# proiect_tsc.net
KiCad netlist of a schematic drawn in EAGLE
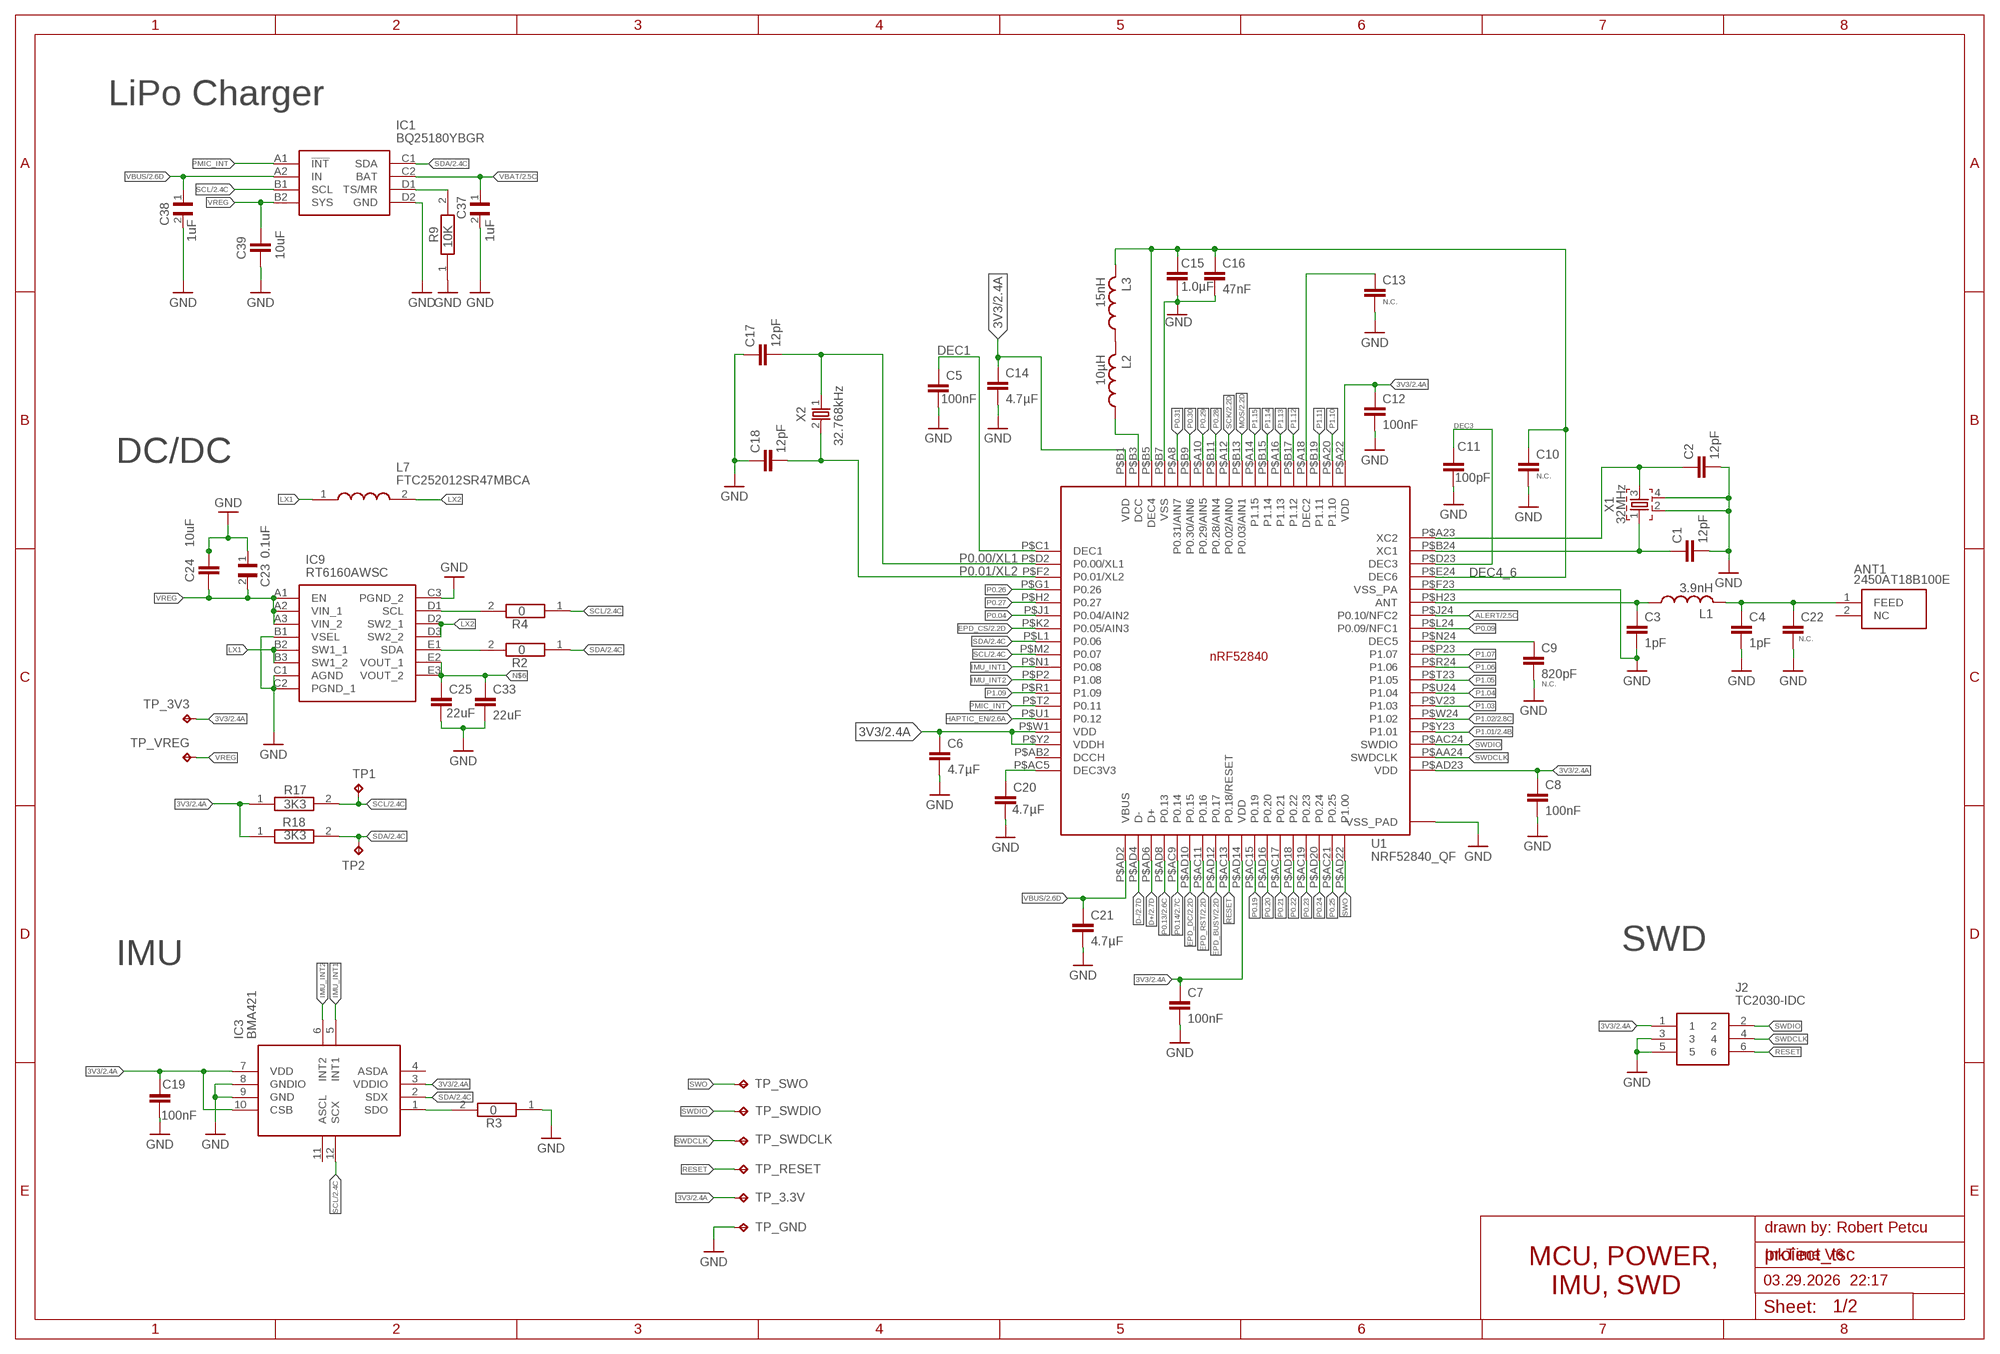
[diagram p0: schematic, sheet 1]
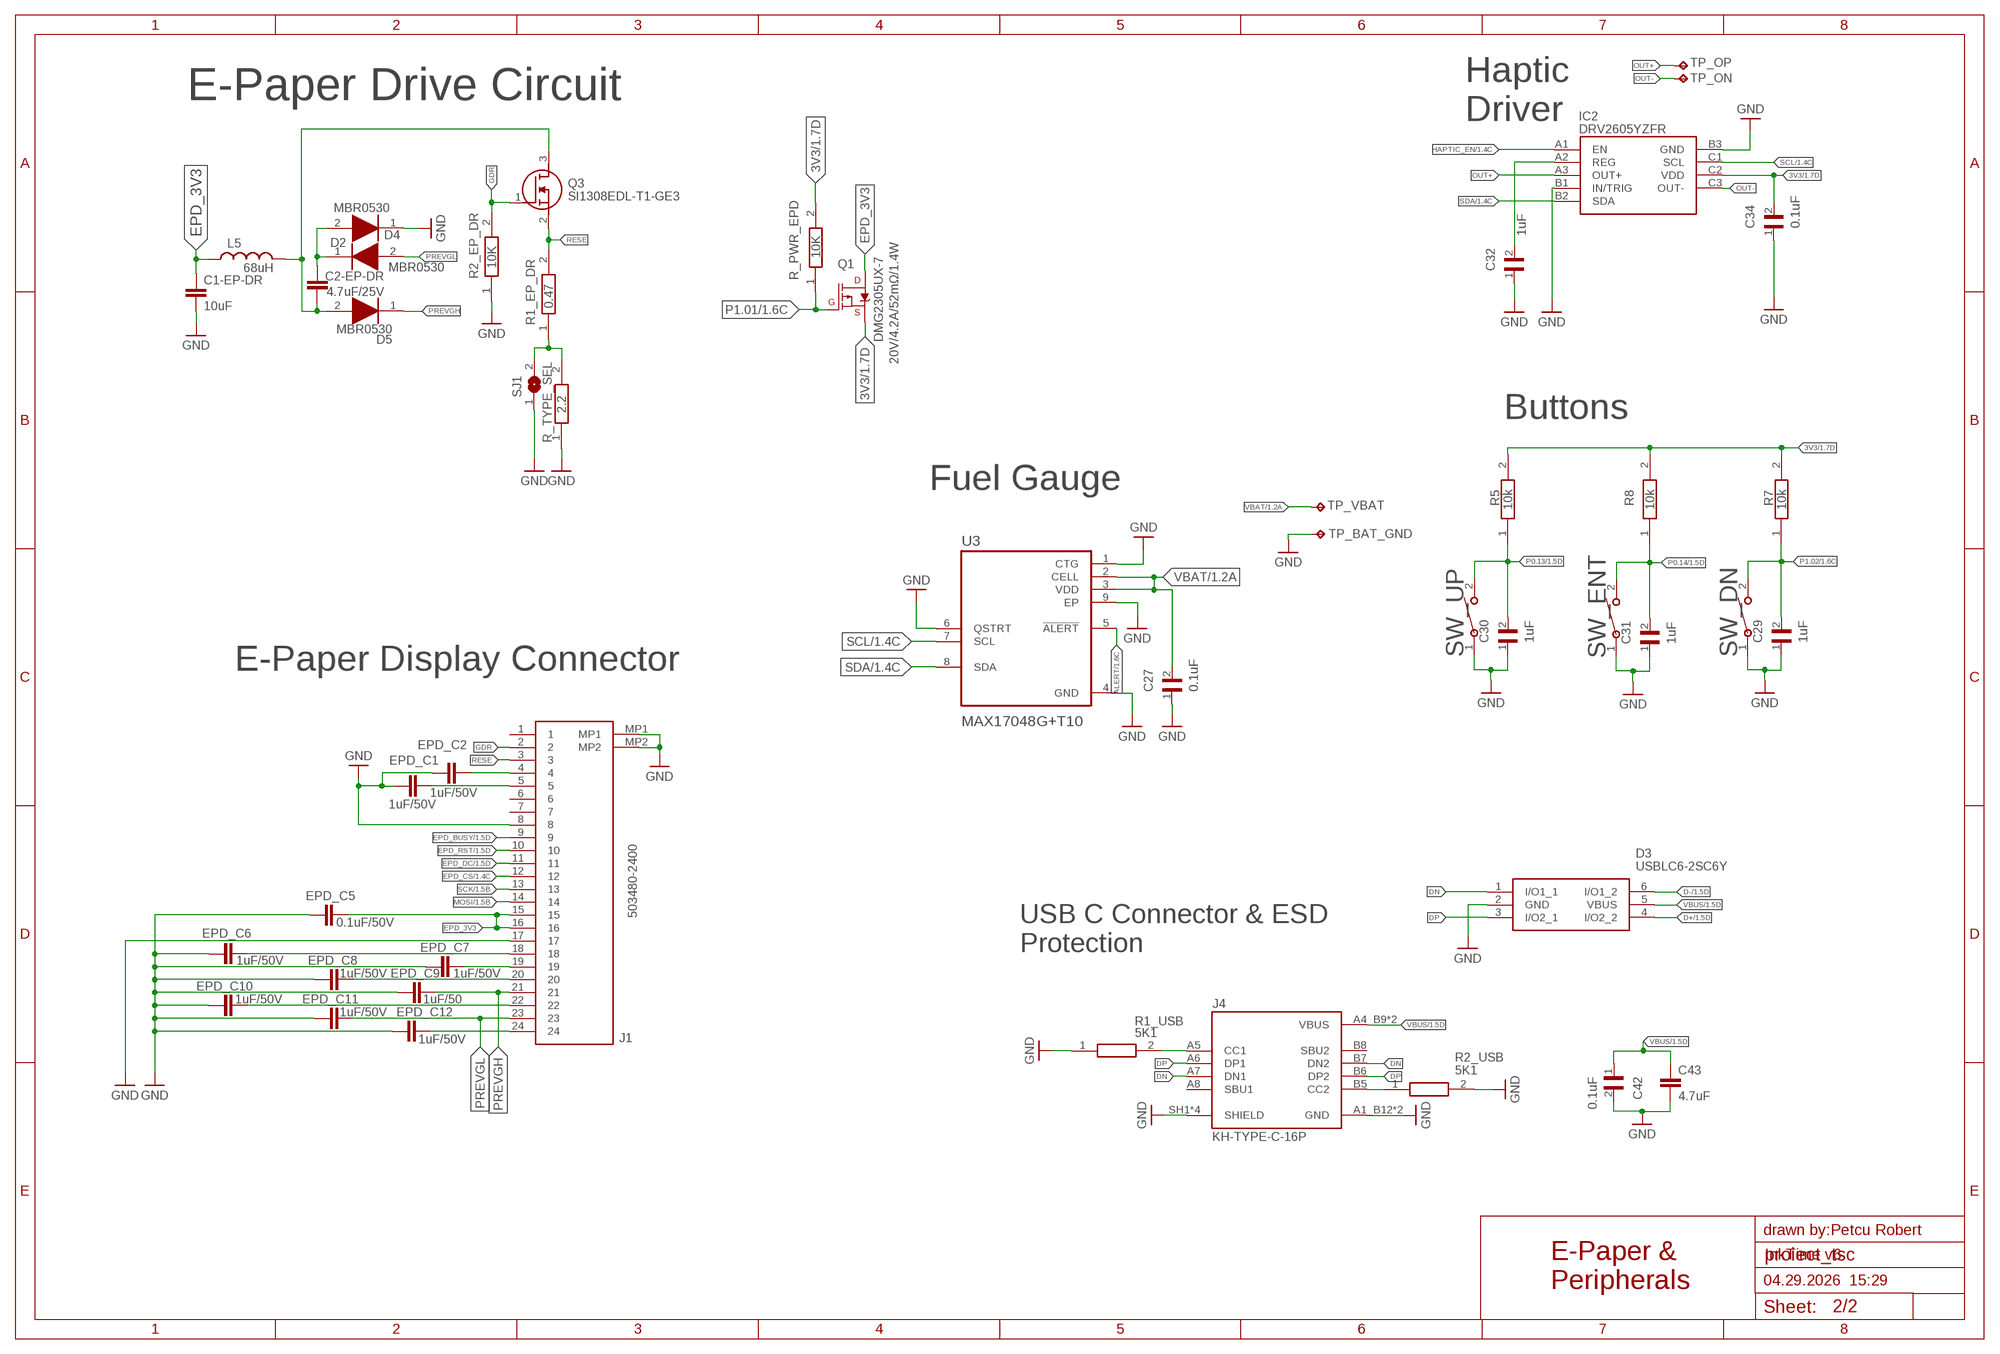
[diagram p1: schematic, sheet 2]

(export (version "E")
  (design (tool "Eeschema 10.0.6"))
  (components
    (comp (ref "C1-EP-DR")
      (value "10uF")
      (footprint "eagle-import:PERFECT_0402_0402")
      (libsource (lib "eagle-import") (part "PERFECT_0402_CAP_0402"))
    )
    (comp (ref "C2-EP-DR")
      (value "4.7uF/25V")
      (footprint "eagle-import:PERFECT_0402_0402")
      (libsource (lib "eagle-import") (part "PERFECT_0402_CAP_0402"))
    )
    (comp (ref "C27")
      (value "0.1uF")
      (footprint "eagle-import:GRM011R60J152KE01L_1_0201")
      (libsource (lib "eagle-import") (part "GRM011R60J152KE01L_1_GRM011R60J152KE01L"))
    )
    (comp (ref "C29")
      (value "1uF")
      (footprint "eagle-import:GRM011R60J152KE01L_1_0201")
      (libsource (lib "eagle-import") (part "GRM011R60J152KE01L_1_GRM011R60J152KE01L"))
    )
    (comp (ref "C30")
      (value "1uF")
      (footprint "eagle-import:GRM011R60J152KE01L_1_0201")
      (libsource (lib "eagle-import") (part "GRM011R60J152KE01L_1_GRM011R60J152KE01L"))
    )
    (comp (ref "C31")
      (value "1uF")
      (footprint "eagle-import:GRM011R60J152KE01L_1_0201")
      (libsource (lib "eagle-import") (part "GRM011R60J152KE01L_1_GRM011R60J152KE01L"))
    )
    (comp (ref "C32")
      (value "1uF")
      (footprint "eagle-import:GRM011R60J152KE01L_1_0201")
      (libsource (lib "eagle-import") (part "GRM011R60J152KE01L_1_GRM011R60J152KE01L"))
    )
    (comp (ref "C34")
      (value "0.1uF")
      (footprint "eagle-import:GRM011R60J152KE01L_1_0201")
      (libsource (lib "eagle-import") (part "GRM011R60J152KE01L_1_GRM011R60J152KE01L"))
    )
    (comp (ref "C42")
      (value "0.1uF")
      (footprint "eagle-import:GRM011R60J152KE01L_1_0201")
      (libsource (lib "eagle-import") (part "GRM011R60J152KE01L_1_GRM011R60J152KE01L"))
    )
    (comp (ref "C43")
      (value "4.7uF")
      (footprint "eagle-import:PERFECT_0402_0402")
      (libsource (lib "eagle-import") (part "PERFECT_0402_CAP_0402"))
    )
    (comp (ref "D2")
      (value "MBR0530")
      (footprint "eagle-import:ESP32_C6_LIBRARY_5_SOD3716X135N")
      (fields (field (name "MF") "ON Semiconductor"))
      (libsource (lib "eagle-import") (part "ESP32_C6_LIBRARY_5_MBR0530"))
    )
    (comp (ref "D3")
      (value "USBLC6-2SC6Y")
      (footprint "eagle-import:ESP32_C6_LIBRARY_3_SOT95P280X145-6N")
      (fields (field (name "MF") "STMicroelectronics"))
      (libsource (lib "eagle-import") (part "ESP32_C6_LIBRARY_3_USBLC6-2SC6Y"))
    )
    (comp (ref "D4")
      (value "MBR0530")
      (footprint "eagle-import:ESP32_C6_LIBRARY_5_SOD3716X135N")
      (fields (field (name "MF") "ON Semiconductor"))
      (libsource (lib "eagle-import") (part "ESP32_C6_LIBRARY_5_MBR0530"))
    )
    (comp (ref "D5")
      (value "MBR0530")
      (footprint "eagle-import:ESP32_C6_LIBRARY_5_SOD3716X135N")
      (fields (field (name "MF") "ON Semiconductor"))
      (libsource (lib "eagle-import") (part "ESP32_C6_LIBRARY_5_MBR0530"))
    )
    (comp (ref "DMG2305UX-7")
      (value "20V/4.2A/52mΩ/1.4W")
      (footprint "eagle-import:ESP32_C6_LIBRARY_4_ESP32_C6_LIBRARY_4_ESP32_C6_LIBRARY_4_ESP32_C6_LIBRARY_4_ESP32_WROVER_SPARKFUN-DISCRETESEMI_SOT23-3")
      (libsource (lib "eagle-import") (part "ESP32_C6_LIBRARY_4_ESP32_WROVER_SPARKFUN-DISCRETESEMI_MOSFET_PCH-DMG2305UX-7"))
    )
    (comp (ref "EPD_C1")
      (value "1uF/50V")
      (footprint "eagle-import:PERFECT_0402_0402")
      (libsource (lib "eagle-import") (part "PERFECT_0402_CAP_0402"))
    )
    (comp (ref "EPD_C2")
      (value "1uF/50V")
      (footprint "eagle-import:PERFECT_0402_0402")
      (libsource (lib "eagle-import") (part "PERFECT_0402_CAP_0402"))
    )
    (comp (ref "EPD_C5")
      (value "0.1uF/50V")
      (footprint "eagle-import:NORDIC_NRF_3_RESC0201_L")
      (libsource (lib "eagle-import") (part "NORDIC_NRF_3_CAPACITOR_0201_L"))
    )
    (comp (ref "EPD_C6")
      (value "1uF/50V")
      (footprint "eagle-import:PERFECT_0402_0402")
      (libsource (lib "eagle-import") (part "PERFECT_0402_CAP_0402"))
    )
    (comp (ref "EPD_C7")
      (value "1uF/50V")
      (footprint "eagle-import:PERFECT_0402_0402")
      (libsource (lib "eagle-import") (part "PERFECT_0402_CAP_0402"))
    )
    (comp (ref "EPD_C8")
      (value "1uF/50V")
      (footprint "eagle-import:PERFECT_0402_0402")
      (libsource (lib "eagle-import") (part "PERFECT_0402_CAP_0402"))
    )
    (comp (ref "EPD_C9")
      (value "1uF/50")
      (footprint "eagle-import:PERFECT_0402_0402")
      (libsource (lib "eagle-import") (part "PERFECT_0402_CAP_0402"))
    )
    (comp (ref "EPD_C10")
      (value "1uF/50V")
      (footprint "eagle-import:PERFECT_0402_0402")
      (libsource (lib "eagle-import") (part "PERFECT_0402_CAP_0402"))
    )
    (comp (ref "EPD_C11")
      (value "1uF/50V")
      (footprint "eagle-import:PERFECT_0402_0402")
      (libsource (lib "eagle-import") (part "PERFECT_0402_CAP_0402"))
    )
    (comp (ref "EPD_C12")
      (value "1uF/50V")
      (footprint "eagle-import:PERFECT_0402_0402")
      (libsource (lib "eagle-import") (part "PERFECT_0402_CAP_0402"))
    )
    (comp (ref "IC2")
      (value "DRV2605YZFR")
      (footprint "eagle-import:DRV2605YZFR_BGA9C50P3X3_144X144X62")
      (libsource (lib "eagle-import") (part "DRV2605YZFR_DRV2605YZFR"))
    )
    (comp (ref "J1")
      (value "503480-2400")
      (footprint "eagle-import:503480-2400_5034802400")
      (fields (field (name "MOUSER_PART_NUMBER") "538-503480-2400"))
      (libsource (lib "eagle-import") (part "503480-2400_503480-2400"))
    )
    (comp (ref "J4")
      (value "KH-TYPE-C-16P")
      (footprint "eagle-import:KH-TYPE-C-16P_KINGHELM_KH-TYPE-C-16P")
      (fields (field (name "MF") "kinghelm"))
      (libsource (lib "eagle-import") (part "KH-TYPE-C-16P_KH-TYPE-C-16P"))
    )
    (comp (ref "L5")
      (value "68uH")
      (footprint "eagle-import:NORDIC_NRF_2_RESC0402_L")
      (libsource (lib "eagle-import") (part "NORDIC_NRF_2_INDUCTOR_0402_L"))
    )
    (comp (ref "Q3")
      (value "SI1308EDL-T1-GE3")
      (footprint "eagle-import:ESP32_C6_LIBRARY_6_SOT65P210X110-3N")
      (fields (field (name "MF") "Vishay Siliconix"))
      (libsource (lib "eagle-import") (part "ESP32_C6_LIBRARY_6_SI1308EDL-T1-GE3"))
    )
    (comp (ref "R1_EP_DR")
      (value "0.47")
      (footprint "eagle-import:CPF0201D7K68C1_0201")
      (libsource (lib "eagle-import") (part "CPF0201D7K68C1_CPF0201D7K68C1"))
    )
    (comp (ref "R1_USB")
      (value "5K1")
      (footprint "eagle-import:CPF0201D7K68C1_0201")
      (libsource (lib "eagle-import") (part "CPF0201D7K68C1_CPF0201D7K68C1"))
    )
    (comp (ref "R2_EP_DR")
      (value "10K")
      (footprint "eagle-import:CPF0201D7K68C1_0201")
      (libsource (lib "eagle-import") (part "CPF0201D7K68C1_CPF0201D7K68C1"))
    )
    (comp (ref "R2_USB")
      (value "5K1")
      (footprint "eagle-import:CPF0201D7K68C1_0201")
      (libsource (lib "eagle-import") (part "CPF0201D7K68C1_CPF0201D7K68C1"))
    )
    (comp (ref "R5")
      (value "10k")
      (footprint "eagle-import:CPF0201D7K68C1_0201")
      (libsource (lib "eagle-import") (part "CPF0201D7K68C1_CPF0201D7K68C1"))
    )
    (comp (ref "R7")
      (value "10k")
      (footprint "eagle-import:CPF0201D7K68C1_0201")
      (libsource (lib "eagle-import") (part "CPF0201D7K68C1_CPF0201D7K68C1"))
    )
    (comp (ref "R8")
      (value "10k")
      (footprint "eagle-import:CPF0201D7K68C1_0201")
      (libsource (lib "eagle-import") (part "CPF0201D7K68C1_CPF0201D7K68C1"))
    )
    (comp (ref "R_PWR_EPD")
      (value "10K")
      (footprint "eagle-import:CPF0201D7K68C1_0201")
      (libsource (lib "eagle-import") (part "CPF0201D7K68C1_CPF0201D7K68C1"))
    )
    (comp (ref "R_TYPE_SEL")
      (value "2.2")
      (footprint "eagle-import:CPF0201D7K68C1_0201")
      (libsource (lib "eagle-import") (part "CPF0201D7K68C1_CPF0201D7K68C1"))
    )
    (comp (ref "SJ1")
      (value "ESP32_C6_LIBRARY_7_JUMPER_SJ")
      (footprint "eagle-import:ESP32_C6_LIBRARY_7_JUMPER_SJ")
      (libsource (lib "eagle-import") (part "ESP32_C6_LIBRARY_7_JUMPER_SJ"))
    )
    (comp (ref "SW_DN")
      (value "2025-10-22_07-23-44_LIBRARY_EVP-AKE31ASW_EVP-AKE31A_PAN")
      (footprint "eagle-import:2025-10-22_07-23-44_LIBRARY_SW_EVP-AKE31A_PAN")
      (fields
        (field (name "MANUFACTURER_PART_NUMBER") "EVP-AKE31A")
        (field (name "COPYRIGHT") "Copyright (C) 2025 Ultra Librarian. All rights reserved.")
      )
      (libsource (lib "eagle-import") (part "2025-10-22_07-23-44_LIBRARY_EVP-AKE31ASW_EVP-AKE31A_PAN"))
    )
    (comp (ref "SW_ENT")
      (value "2025-10-22_07-23-44_LIBRARY_EVP-AKE31ASW_EVP-AKE31A_PAN")
      (footprint "eagle-import:2025-10-22_07-23-44_LIBRARY_SW_EVP-AKE31A_PAN")
      (fields
        (field (name "MANUFACTURER_PART_NUMBER") "EVP-AKE31A")
        (field (name "COPYRIGHT") "Copyright (C) 2025 Ultra Librarian. All rights reserved.")
      )
      (libsource (lib "eagle-import") (part "2025-10-22_07-23-44_LIBRARY_EVP-AKE31ASW_EVP-AKE31A_PAN"))
    )
    (comp (ref "SW_UP")
      (value "2025-10-22_07-23-44_LIBRARY_EVP-AKE31ASW_EVP-AKE31A_PAN")
      (footprint "eagle-import:2025-10-22_07-23-44_LIBRARY_SW_EVP-AKE31A_PAN")
      (fields
        (field (name "MANUFACTURER_PART_NUMBER") "EVP-AKE31A")
        (field (name "COPYRIGHT") "Copyright (C) 2025 Ultra Librarian. All rights reserved.")
      )
      (libsource (lib "eagle-import") (part "2025-10-22_07-23-44_LIBRARY_EVP-AKE31ASW_EVP-AKE31A_PAN"))
    )
    (comp (ref "TP_BAT_GND")
      (value "HECTOR_WATCH_1_TPTP20R")
      (footprint "eagle-import:HECTOR_WATCH_1_TP20R")
      (libsource (lib "eagle-import") (part "HECTOR_WATCH_1_TPTP20R"))
    )
    (comp (ref "TP_ON")
      (value "HECTOR_WATCH_1_TPTP20R")
      (footprint "eagle-import:HECTOR_WATCH_1_TP20R")
      (libsource (lib "eagle-import") (part "HECTOR_WATCH_1_TPTP20R"))
    )
    (comp (ref "TP_OP")
      (value "HECTOR_WATCH_1_TPTP20R")
      (footprint "eagle-import:HECTOR_WATCH_1_TP20R")
      (libsource (lib "eagle-import") (part "HECTOR_WATCH_1_TPTP20R"))
    )
    (comp (ref "TP_VBAT")
      (value "HECTOR_WATCH_1_TPTP20R")
      (footprint "eagle-import:HECTOR_WATCH_1_TP20R")
      (libsource (lib "eagle-import") (part "HECTOR_WATCH_1_TPTP20R"))
    )
    (comp (ref "U3")
      (value "MAX17048G+T10")
      (footprint "eagle-import:ESP32_C6_LIBRARY_SON50P200X200X80-9N")
      (fields (field (name "MF") "Analog Devices"))
      (libsource (lib "eagle-import") (part "ESP32_C6_LIBRARY_MAX17048G+T10"))
    )
    (comp (ref "ANT1")
      (value "2450AT18B100E")
      (footprint "eagle-import:2450AT18B100E_ANTC3216X140N")
      (fields (field (name "MOUSER_PART_NUMBER") "609-2450AT18B100E"))
      (libsource (lib "eagle-import") (part "2450AT18B100E_2450AT18B100E"))
    )
    (comp (ref "C1")
      (value "12pF")
      (footprint "eagle-import:NORDIC_NRF_3_RESC0201_L")
      (libsource (lib "eagle-import") (part "NORDIC_NRF_3_CAPACITOR_0201_L"))
    )
    (comp (ref "C2")
      (value "12pF")
      (footprint "eagle-import:NORDIC_NRF_3_RESC0201_L")
      (libsource (lib "eagle-import") (part "NORDIC_NRF_3_CAPACITOR_0201_L"))
    )
    (comp (ref "C3")
      (value "1pF")
      (footprint "eagle-import:NORDIC_NRF_3_RESC0201_L")
      (libsource (lib "eagle-import") (part "NORDIC_NRF_3_CAPACITOR_0201_L"))
    )
    (comp (ref "C4")
      (value "1pF")
      (footprint "eagle-import:NORDIC_NRF_3_RESC0201_L")
      (libsource (lib "eagle-import") (part "NORDIC_NRF_3_CAPACITOR_0201_L"))
    )
    (comp (ref "C5")
      (value "100nF")
      (footprint "eagle-import:NORDIC_NRF_3_RESC0201_L")
      (libsource (lib "eagle-import") (part "NORDIC_NRF_3_CAPACITOR_0201_L"))
    )
    (comp (ref "C6")
      (value "4.7µF")
      (footprint "eagle-import:PERFECT_0402_0402")
      (libsource (lib "eagle-import") (part "PERFECT_0402_CAP_0402"))
    )
    (comp (ref "C7")
      (value "100nF")
      (footprint "eagle-import:NORDIC_NRF_3_RESC0201_L")
      (libsource (lib "eagle-import") (part "NORDIC_NRF_3_CAPACITOR_0201_L"))
    )
    (comp (ref "C8")
      (value "100nF")
      (footprint "eagle-import:NORDIC_NRF_3_RESC0201_L")
      (libsource (lib "eagle-import") (part "NORDIC_NRF_3_CAPACITOR_0201_L"))
    )
    (comp (ref "C9")
      (value "820pF")
      (footprint "eagle-import:NORDIC_NRF_3_RESC0201_L")
      (libsource (lib "eagle-import") (part "NORDIC_NRF_3_CAPACITOR_0201_L"))
    )
    (comp (ref "C10")
      (value "NORDIC_NRF_3_CAPACITOR_0201_L")
      (footprint "eagle-import:NORDIC_NRF_3_RESC0201_L")
      (libsource (lib "eagle-import") (part "NORDIC_NRF_3_CAPACITOR_0201_L"))
    )
    (comp (ref "C11")
      (value "100pF")
      (footprint "eagle-import:NORDIC_NRF_3_RESC0201_L")
      (libsource (lib "eagle-import") (part "NORDIC_NRF_3_CAPACITOR_0201_L"))
    )
    (comp (ref "C12")
      (value "100nF")
      (footprint "eagle-import:NORDIC_NRF_3_RESC0201_L")
      (libsource (lib "eagle-import") (part "NORDIC_NRF_3_CAPACITOR_0201_L"))
    )
    (comp (ref "C13")
      (value "NORDIC_NRF_3_CAPACITOR_0201_L")
      (footprint "eagle-import:NORDIC_NRF_3_RESC0201_L")
      (libsource (lib "eagle-import") (part "NORDIC_NRF_3_CAPACITOR_0201_L"))
    )
    (comp (ref "C14")
      (value "4.7µF")
      (footprint "eagle-import:PERFECT_0402_0402")
      (libsource (lib "eagle-import") (part "PERFECT_0402_CAP_0402"))
    )
    (comp (ref "C15")
      (value "1.0µF")
      (footprint "eagle-import:PERFECT_0402_0402")
      (libsource (lib "eagle-import") (part "PERFECT_0402_CAP_0402"))
    )
    (comp (ref "C16")
      (value "47nF")
      (footprint "eagle-import:NORDIC_NRF_3_RESC0201_L")
      (libsource (lib "eagle-import") (part "NORDIC_NRF_3_CAPACITOR_0201_L"))
    )
    (comp (ref "C17")
      (value "12pF")
      (footprint "eagle-import:NORDIC_NRF_3_RESC0201_L")
      (libsource (lib "eagle-import") (part "NORDIC_NRF_3_CAPACITOR_0201_L"))
    )
    (comp (ref "C18")
      (value "12pF")
      (footprint "eagle-import:NORDIC_NRF_3_RESC0201_L")
      (libsource (lib "eagle-import") (part "NORDIC_NRF_3_CAPACITOR_0201_L"))
    )
    (comp (ref "C19")
      (value "100nF")
      (footprint "eagle-import:NORDIC_NRF_3_RESC0201_L")
      (libsource (lib "eagle-import") (part "NORDIC_NRF_3_CAPACITOR_0201_L"))
    )
    (comp (ref "C20")
      (value "4.7µF")
      (footprint "eagle-import:PERFECT_0402_0402")
      (libsource (lib "eagle-import") (part "PERFECT_0402_CAP_0402"))
    )
    (comp (ref "C21")
      (value "4.7µF")
      (footprint "eagle-import:PERFECT_0402_0402")
      (libsource (lib "eagle-import") (part "PERFECT_0402_CAP_0402"))
    )
    (comp (ref "C22")
      (value "NORDIC_NRF_3_CAPACITOR_0201_L")
      (footprint "eagle-import:NORDIC_NRF_3_RESC0201_L")
      (libsource (lib "eagle-import") (part "NORDIC_NRF_3_CAPACITOR_0201_L"))
    )
    (comp (ref "C23")
      (value "0.1uF")
      (footprint "eagle-import:GRM011R60J152KE01L_1_0201")
      (libsource (lib "eagle-import") (part "GRM011R60J152KE01L_1_GRM011R60J152KE01L"))
    )
    (comp (ref "C24")
      (value "10uF")
      (footprint "eagle-import:PERFECT_0402_0402")
      (libsource (lib "eagle-import") (part "PERFECT_0402_CAP_0402"))
    )
    (comp (ref "C25")
      (value "22uF")
      (footprint "eagle-import:PERFECT_0402_0402")
      (libsource (lib "eagle-import") (part "PERFECT_0402_CAP_0402"))
    )
    (comp (ref "C33")
      (value "22uF")
      (footprint "eagle-import:PERFECT_0402_0402")
      (libsource (lib "eagle-import") (part "PERFECT_0402_CAP_0402"))
    )
    (comp (ref "C37")
      (value "1uF")
      (footprint "eagle-import:GRM011R60J152KE01L_1_0201")
      (libsource (lib "eagle-import") (part "GRM011R60J152KE01L_1_GRM011R60J152KE01L"))
    )
    (comp (ref "C38")
      (value "1uF")
      (footprint "eagle-import:GRM011R60J152KE01L_1_0201")
      (libsource (lib "eagle-import") (part "GRM011R60J152KE01L_1_GRM011R60J152KE01L"))
    )
    (comp (ref "C39")
      (value "10uF")
      (footprint "eagle-import:PERFECT_0402_0402")
      (libsource (lib "eagle-import") (part "PERFECT_0402_CAP_0402"))
    )
    (comp (ref "IC1")
      (value "BQ25180YBGR")
      (footprint "eagle-import:BQ25180YBGR_BGA8C40P2X4_100X155X50")
      (fields (field (name "MOUSER_PART_NUMBER") "595-BQ25180YBGR"))
      (libsource (lib "eagle-import") (part "BQ25180YBGR_BQ25180YBGR"))
    )
    (comp (ref "IC3")
      (value "BMA421")
      (footprint "eagle-import:BMA423_BMA423")
      (fields (field (name "ARROW_PART_NUMBER") "BMA423") (field (name "MOUSER_PART_NUMBER") "262-BMA423"))
      (libsource (lib "eagle-import") (part "BMA423_BMA423"))
    )
    (comp (ref "IC9")
      (value "RT6160AWSC")
      (footprint "eagle-import:RT6160AWSC_BGA15C40P3X5_140X230X60")
      (fields (field (name "MOUSER_PART_NUMBER") "835-RT6160AWSC"))
      (libsource (lib "eagle-import") (part "RT6160AWSC_RT6160AWSC"))
    )
    (comp (ref "J2")
      (value "TC2030-IDC")
      (footprint "eagle-import:TC2030-IDC_TC2030IDC")
      (libsource (lib "eagle-import") (part "TC2030-IDC_TC2030-IDC"))
    )
    (comp (ref "L1")
      (value "3.9nH")
      (footprint "eagle-import:NORDIC_NRF_2_RESC0402_L")
      (libsource (lib "eagle-import") (part "NORDIC_NRF_2_INDUCTOR_0402_L"))
    )
    (comp (ref "L2")
      (value "10µH")
      (footprint "eagle-import:NORDIC_NRF_2_RESC0402_L")
      (libsource (lib "eagle-import") (part "NORDIC_NRF_2_INDUCTOR_0402_L"))
    )
    (comp (ref "L3")
      (value "15nH")
      (footprint "eagle-import:NORDIC_NRF_2_RESC0402_L")
      (libsource (lib "eagle-import") (part "NORDIC_NRF_2_INDUCTOR_0402_L"))
    )
    (comp (ref "L7")
      (value "FTC252012SR47MBCA")
      (footprint "eagle-import:MLP2016SR47MT0S1_INDC2016X100N")
      (libsource (lib "eagle-import") (part "MLP2016SR47MT0S1_FTC252012SR47MBCA"))
    )
    (comp (ref "R2")
      (value "0")
      (footprint "eagle-import:CPF0201D7K68C1_0201")
      (libsource (lib "eagle-import") (part "CPF0201D7K68C1_CPF0201D7K68C1"))
    )
    (comp (ref "R3")
      (value "0")
      (footprint "eagle-import:CPF0201D7K68C1_0201")
      (libsource (lib "eagle-import") (part "CPF0201D7K68C1_CPF0201D7K68C1"))
    )
    (comp (ref "R4")
      (value "0")
      (footprint "eagle-import:CPF0201D7K68C1_0201")
      (libsource (lib "eagle-import") (part "CPF0201D7K68C1_CPF0201D7K68C1"))
    )
    (comp (ref "R9")
      (value "10K")
      (footprint "eagle-import:CPF0201D7K68C1_0201")
      (libsource (lib "eagle-import") (part "CPF0201D7K68C1_CPF0201D7K68C1"))
    )
    (comp (ref "R17")
      (value "3K3")
      (footprint "eagle-import:CPF0201D7K68C1_0201")
      (libsource (lib "eagle-import") (part "CPF0201D7K68C1_CPF0201D7K68C1"))
    )
    (comp (ref "R18")
      (value "3K3")
      (footprint "eagle-import:CPF0201D7K68C1_0201")
      (libsource (lib "eagle-import") (part "CPF0201D7K68C1_CPF0201D7K68C1"))
    )
    (comp (ref "TP1")
      (value "HECTOR_WATCH_1_TPTP20R")
      (footprint "eagle-import:HECTOR_WATCH_1_TP20R")
      (libsource (lib "eagle-import") (part "HECTOR_WATCH_1_TPTP20R"))
    )
    (comp (ref "TP2")
      (value "HECTOR_WATCH_1_TPTP20R")
      (footprint "eagle-import:HECTOR_WATCH_1_TP20R")
      (libsource (lib "eagle-import") (part "HECTOR_WATCH_1_TPTP20R"))
    )
    (comp (ref "TP_3.3V")
      (value "HECTOR_WATCH_1_TPTP20R")
      (footprint "eagle-import:HECTOR_WATCH_1_TP20R")
      (libsource (lib "eagle-import") (part "HECTOR_WATCH_1_TPTP20R"))
    )
    (comp (ref "TP_3V3")
      (value "HECTOR_WATCH_1_TPTP20R")
      (footprint "eagle-import:HECTOR_WATCH_1_TP20R")
      (libsource (lib "eagle-import") (part "HECTOR_WATCH_1_TPTP20R"))
    )
    (comp (ref "TP_GND")
      (value "HECTOR_WATCH_1_TPTP20R")
      (footprint "eagle-import:HECTOR_WATCH_1_TP20R")
      (libsource (lib "eagle-import") (part "HECTOR_WATCH_1_TPTP20R"))
    )
    (comp (ref "TP_RESET")
      (value "HECTOR_WATCH_1_TPTP20R")
      (footprint "eagle-import:HECTOR_WATCH_1_TP20R")
      (libsource (lib "eagle-import") (part "HECTOR_WATCH_1_TPTP20R"))
    )
    (comp (ref "TP_SWDCLK")
      (value "HECTOR_WATCH_1_TPTP20R")
      (footprint "eagle-import:HECTOR_WATCH_1_TP20R")
      (libsource (lib "eagle-import") (part "HECTOR_WATCH_1_TPTP20R"))
    )
    (comp (ref "TP_SWDIO")
      (value "HECTOR_WATCH_1_TPTP20R")
      (footprint "eagle-import:HECTOR_WATCH_1_TP20R")
      (libsource (lib "eagle-import") (part "HECTOR_WATCH_1_TPTP20R"))
    )
    (comp (ref "TP_SWO")
      (value "HECTOR_WATCH_1_TPTP20R")
      (footprint "eagle-import:HECTOR_WATCH_1_TP20R")
      (libsource (lib "eagle-import") (part "HECTOR_WATCH_1_TPTP20R"))
    )
    (comp (ref "TP_VREG")
      (value "HECTOR_WATCH_1_TPTP20R")
      (footprint "eagle-import:HECTOR_WATCH_1_TP20R")
      (libsource (lib "eagle-import") (part "HECTOR_WATCH_1_TPTP20R"))
    )
    (comp (ref "U1")
      (value "NRF52840_QF")
      (footprint "eagle-import:NORDIC_NRF_4_AQFN50P700X700X85_HS-74N")
      (libsource (lib "eagle-import") (part "NORDIC_NRF_4_NRF52840_QF"))
    )
    (comp (ref "X1")
      (value "32MHz")
      (footprint "eagle-import:NORDIC_NRF_BT-XTAL_2016_N")
      (libsource (lib "eagle-import") (part "NORDIC_NRF_XTAL_32MHZ"))
    )
    (comp (ref "X2")
      (value "32.768kHz")
      (footprint "eagle-import:NORDIC_NRF_1_XTAL_3215_N")
      (libsource (lib "eagle-import") (part "NORDIC_NRF_1_XTAL_32KHZ"))
    )
  )
  (nets
    (net (code "1") (name "3V3{slash}1.7D") (class "Default")
      (node (ref "C34") (pin "2") (pinfunction "2_2") (pintype "passive"))
      (node (ref "DMG2305UX-7") (pin "2") (pinfunction "S_2") (pintype "bidirectional"))
      (node (ref "IC2") (pin "C2") (pinfunction "VDD_C2") (pintype "bidirectional"))
      (node (ref "R5") (pin "2") (pinfunction "2_2") (pintype "bidirectional"))
      (node (ref "R7") (pin "2") (pinfunction "2_2") (pintype "bidirectional"))
      (node (ref "R8") (pin "2") (pinfunction "2_2") (pintype "bidirectional"))
      (node (ref "R_PWR_EPD") (pin "2") (pinfunction "2_2") (pintype "bidirectional"))
    )
    (net (code "2") (name "3V3{slash}2.4A") (class "Default")
      (node (ref "C12") (pin "1") (pinfunction "1_1") (pintype "passive"))
      (node (ref "C14") (pin "1") (pinfunction "1_1") (pintype "passive"))
      (node (ref "C19") (pin "1") (pinfunction "1_1") (pintype "passive"))
      (node (ref "C6") (pin "1") (pinfunction "1_1") (pintype "passive"))
      (node (ref "C7") (pin "1") (pinfunction "1_1") (pintype "passive"))
      (node (ref "C8") (pin "1") (pinfunction "1_1") (pintype "passive"))
      (node (ref "IC3") (pin "10") (pinfunction "CSB_10") (pintype "bidirectional"))
      (node (ref "IC3") (pin "3") (pinfunction "VDDIO_3") (pintype "bidirectional"))
      (node (ref "IC3") (pin "7") (pinfunction "VDD_7") (pintype "bidirectional"))
      (node (ref "J2") (pin "1") (pinfunction "1_1") (pintype "bidirectional"))
      (node (ref "R17") (pin "1") (pinfunction "1_1") (pintype "bidirectional"))
      (node (ref "R18") (pin "1") (pinfunction "1_1") (pintype "bidirectional"))
      (node (ref "TP_3.3V") (pin "TP") (pinfunction "TP_TP") (pintype "input"))
      (node (ref "TP_3V3") (pin "TP") (pinfunction "TP_TP") (pintype "input"))
      (node (ref "U1") (pin "P$A22") (pinfunction "VDD_P$A22") (pintype "power_in"))
      (node (ref "U1") (pin "P$AD14") (pinfunction "VDD_P$AD14") (pintype "power_in"))
      (node (ref "U1") (pin "P$AD23") (pinfunction "VDD_P$AD23") (pintype "power_in"))
      (node (ref "U1") (pin "P$B1") (pinfunction "VDD_P$B1") (pintype "power_in"))
      (node (ref "U1") (pin "P$W1") (pinfunction "VDD_P$W1") (pintype "power_in"))
      (node (ref "U1") (pin "P$Y2") (pinfunction "VDDH_P$Y2") (pintype "power_in"))
    )
    (net (code "3") (name "ALERT{slash}1.6C") (class "Default")
      (node (ref "U3") (pin "5") (pinfunction "~{ALERT}_5") (pintype "output"))
    )
    (net (code "4") (name "ALERT{slash}2.5C") (class "Default")
      (node (ref "U1") (pin "P$J24") (pinfunction "P0.10/NFC2_P$J24") (pintype "bidirectional"))
    )
    (net (code "5") (name "D+{slash}1.5D") (class "Default")
      (node (ref "D3") (pin "4") (pinfunction "I/O2_2_4") (pintype "bidirectional"))
    )
    (net (code "6") (name "D+{slash}2.7D") (class "Default")
      (node (ref "U1") (pin "P$AD6") (pinfunction "D+_P$AD6") (pintype "bidirectional"))
    )
    (net (code "7") (name "D-{slash}1.5D") (class "Default")
      (node (ref "D3") (pin "6") (pinfunction "I/O1_2_6") (pintype "bidirectional"))
    )
    (net (code "8") (name "D-{slash}2.7D") (class "Default")
      (node (ref "U1") (pin "P$AD4") (pinfunction "D-_P$AD4") (pintype "bidirectional"))
    )
    (net (code "9") (name "DEC1") (class "Default")
      (node (ref "C5") (pin "1") (pinfunction "1_1") (pintype "passive"))
      (node (ref "U1") (pin "P$C1") (pinfunction "DEC1_P$C1") (pintype "power_in"))
    )
    (net (code "10") (name "DEC3") (class "Default")
      (node (ref "C11") (pin "1") (pinfunction "1_1") (pintype "passive"))
      (node (ref "U1") (pin "P$D23") (pinfunction "DEC3_P$D23") (pintype "bidirectional"))
    )
    (net (code "11") (name "DEC4_6") (class "Default")
      (node (ref "C10") (pin "1") (pinfunction "1_1") (pintype "passive"))
      (node (ref "C15") (pin "1") (pinfunction "1_1") (pintype "passive"))
      (node (ref "C16") (pin "1") (pinfunction "1_1") (pintype "passive"))
      (node (ref "L3") (pin "2") (pinfunction "2_2") (pintype "passive"))
      (node (ref "U1") (pin "P$B5") (pinfunction "DEC4_P$B5") (pintype "power_in"))
      (node (ref "U1") (pin "P$E24") (pinfunction "DEC6_P$E24") (pintype "bidirectional"))
    )
    (net (code "12") (name "DN") (class "Default")
      (node (ref "D3") (pin "1") (pinfunction "I/O1_1_1") (pintype "bidirectional"))
      (node (ref "J4") (pin "A7") (pinfunction "DN1_A7") (pintype "bidirectional"))
      (node (ref "J4") (pin "B7") (pinfunction "DN2_B7") (pintype "bidirectional"))
    )
    (net (code "13") (name "DP") (class "Default")
      (node (ref "D3") (pin "3") (pinfunction "I/O2_1_3") (pintype "bidirectional"))
      (node (ref "J4") (pin "A6") (pinfunction "DP1_A6") (pintype "bidirectional"))
      (node (ref "J4") (pin "B6") (pinfunction "DP2_B6") (pintype "bidirectional"))
    )
    (net (code "14") (name "EPD_3V3") (class "Default")
      (node (ref "C1-EP-DR") (pin "1") (pinfunction "1_1") (pintype "passive"))
      (node (ref "DMG2305UX-7") (pin "3") (pinfunction "D_3") (pintype "bidirectional"))
      (node (ref "EPD_C5") (pin "2") (pinfunction "2_2") (pintype "passive"))
      (node (ref "J1") (pin "15") (pinfunction "15_15") (pintype "bidirectional"))
      (node (ref "J1") (pin "16") (pinfunction "16_16") (pintype "bidirectional"))
      (node (ref "L5") (pin "1") (pinfunction "1_1") (pintype "passive"))
    )
    (net (code "15") (name "EPD_BUSY{slash}1.5D") (class "Default")
      (node (ref "J1") (pin "9") (pinfunction "9_9") (pintype "bidirectional"))
    )
    (net (code "16") (name "EPD_BUSY{slash}2.2D") (class "Default")
      (node (ref "U1") (pin "P$AD12") (pinfunction "P0.17_P$AD12") (pintype "bidirectional"))
    )
    (net (code "17") (name "EPD_CS{slash}1.4C") (class "Default")
      (node (ref "J1") (pin "12") (pinfunction "12_12") (pintype "bidirectional"))
    )
    (net (code "18") (name "EPD_CS{slash}2.2D") (class "Default")
      (node (ref "U1") (pin "P$K2") (pinfunction "P0.05/AIN3_P$K2") (pintype "bidirectional"))
    )
    (net (code "19") (name "EPD_DC{slash}1.5D") (class "Default")
      (node (ref "J1") (pin "11") (pinfunction "11_11") (pintype "bidirectional"))
    )
    (net (code "20") (name "EPD_DC{slash}2.2D") (class "Default")
      (node (ref "U1") (pin "P$AD10") (pinfunction "P0.15_P$AD10") (pintype "bidirectional"))
    )
    (net (code "21") (name "EPD_RST{slash}1.5D") (class "Default")
      (node (ref "J1") (pin "10") (pinfunction "10_10") (pintype "bidirectional"))
    )
    (net (code "22") (name "EPD_RST{slash}2.2D") (class "Default")
      (node (ref "U1") (pin "P$AC11") (pinfunction "P0.16_P$AC11") (pintype "bidirectional"))
    )
    (net (code "23") (name "GDR") (class "Default")
      (node (ref "J1") (pin "2") (pinfunction "2_2") (pintype "bidirectional"))
      (node (ref "Q3") (pin "1") (pinfunction "G_1") (pintype "bidirectional"))
      (node (ref "R2_EP_DR") (pin "2") (pinfunction "2_2") (pintype "bidirectional"))
    )
    (net (code "24") (name "GND") (class "Default")
      (node (ref "C1") (pin "2") (pinfunction "2_2") (pintype "passive"))
      (node (ref "C1-EP-DR") (pin "2") (pinfunction "2_2") (pintype "passive"))
      (node (ref "C10") (pin "2") (pinfunction "2_2") (pintype "passive"))
      (node (ref "C11") (pin "2") (pinfunction "2_2") (pintype "passive"))
      (node (ref "C12") (pin "2") (pinfunction "2_2") (pintype "passive"))
      (node (ref "C13") (pin "2") (pinfunction "2_2") (pintype "passive"))
      (node (ref "C14") (pin "2") (pinfunction "2_2") (pintype "passive"))
      (node (ref "C15") (pin "2") (pinfunction "2_2") (pintype "passive"))
      (node (ref "C16") (pin "2") (pinfunction "2_2") (pintype "passive"))
      (node (ref "C17") (pin "1") (pinfunction "1_1") (pintype "passive"))
      (node (ref "C18") (pin "1") (pinfunction "1_1") (pintype "passive"))
      (node (ref "C19") (pin "2") (pinfunction "2_2") (pintype "passive"))
      (node (ref "C2") (pin "2") (pinfunction "2_2") (pintype "passive"))
      (node (ref "C20") (pin "2") (pinfunction "2_2") (pintype "passive"))
      (node (ref "C21") (pin "2") (pinfunction "2_2") (pintype "passive"))
      (node (ref "C22") (pin "2") (pinfunction "2_2") (pintype "passive"))
      (node (ref "C23") (pin "1") (pinfunction "1_1") (pintype "passive"))
      (node (ref "C24") (pin "1") (pinfunction "1_1") (pintype "passive"))
      (node (ref "C25") (pin "2") (pinfunction "2_2") (pintype "passive"))
      (node (ref "C27") (pin "1") (pinfunction "1_1") (pintype "passive"))
      (node (ref "C29") (pin "1") (pinfunction "1_1") (pintype "passive"))
      (node (ref "C3") (pin "2") (pinfunction "2_2") (pintype "passive"))
      (node (ref "C30") (pin "1") (pinfunction "1_1") (pintype "passive"))
      (node (ref "C31") (pin "1") (pinfunction "1_1") (pintype "passive"))
      (node (ref "C32") (pin "1") (pinfunction "1_1") (pintype "passive"))
      (node (ref "C33") (pin "2") (pinfunction "2_2") (pintype "passive"))
      (node (ref "C34") (pin "1") (pinfunction "1_1") (pintype "passive"))
      (node (ref "C37") (pin "2") (pinfunction "2_2") (pintype "passive"))
      (node (ref "C38") (pin "2") (pinfunction "2_2") (pintype "passive"))
      (node (ref "C39") (pin "2") (pinfunction "2_2") (pintype "passive"))
      (node (ref "C4") (pin "2") (pinfunction "2_2") (pintype "passive"))
      (node (ref "C42") (pin "2") (pinfunction "2_2") (pintype "passive"))
      (node (ref "C43") (pin "2") (pinfunction "2_2") (pintype "passive"))
      (node (ref "C5") (pin "2") (pinfunction "2_2") (pintype "passive"))
      (node (ref "C6") (pin "2") (pinfunction "2_2") (pintype "passive"))
      (node (ref "C7") (pin "2") (pinfunction "2_2") (pintype "passive"))
      (node (ref "C8") (pin "2") (pinfunction "2_2") (pintype "passive"))
      (node (ref "C9") (pin "2") (pinfunction "2_2") (pintype "passive"))
      (node (ref "D3") (pin "2") (pinfunction "GND_2") (pintype "bidirectional"))
      (node (ref "D4") (pin "1") (pinfunction "K_1") (pintype "bidirectional"))
      (node (ref "EPD_C1") (pin "1") (pinfunction "1_1") (pintype "passive"))
      (node (ref "EPD_C10") (pin "1") (pinfunction "1_1") (pintype "passive"))
      (node (ref "EPD_C11") (pin "1") (pinfunction "1_1") (pintype "passive"))
      (node (ref "EPD_C12") (pin "1") (pinfunction "1_1") (pintype "passive"))
      (node (ref "EPD_C2") (pin "1") (pinfunction "1_1") (pintype "passive"))
      (node (ref "EPD_C5") (pin "1") (pinfunction "1_1") (pintype "passive"))
      (node (ref "EPD_C6") (pin "1") (pinfunction "1_1") (pintype "passive"))
      (node (ref "EPD_C7") (pin "1") (pinfunction "1_1") (pintype "passive"))
      (node (ref "EPD_C8") (pin "1") (pinfunction "1_1") (pintype "passive"))
      (node (ref "EPD_C9") (pin "1") (pinfunction "1_1") (pintype "passive"))
      (node (ref "IC1") (pin "D2") (pinfunction "GND_D2") (pintype "bidirectional"))
      (node (ref "IC2") (pin "B1") (pinfunction "IN/TRIG_B1") (pintype "bidirectional"))
      (node (ref "IC2") (pin "B3") (pinfunction "GND_B3") (pintype "bidirectional"))
      (node (ref "IC3") (pin "8") (pinfunction "GNDIO_8") (pintype "bidirectional"))
      (node (ref "IC3") (pin "9") (pinfunction "GND_9") (pintype "bidirectional"))
      (node (ref "IC9") (pin "B1") (pinfunction "VSEL_B1") (pintype "bidirectional"))
      (node (ref "IC9") (pin "C1") (pinfunction "AGND_C1") (pintype "bidirectional"))
      (node (ref "IC9") (pin "C2") (pinfunction "PGND_1_C2") (pintype "bidirectional"))
      (node (ref "IC9") (pin "C3") (pinfunction "PGND_2_C3") (pintype "bidirectional"))
      (node (ref "J1") (pin "17") (pinfunction "17_17") (pintype "bidirectional"))
      (node (ref "J1") (pin "8") (pinfunction "8_8") (pintype "bidirectional"))
      (node (ref "J1") (pin "MP1") (pinfunction "MP1_MP1") (pintype "bidirectional"))
      (node (ref "J1") (pin "MP2") (pinfunction "MP2_MP2") (pintype "bidirectional"))
      (node (ref "J2") (pin "3") (pinfunction "3_3") (pintype "bidirectional"))
      (node (ref "J2") (pin "5") (pinfunction "5_5") (pintype "bidirectional"))
      (node (ref "J4") (pin "A12_B1") (pinfunction "GND_A12_B1") (pintype "power_in"))
      (node (ref "J4") (pin "A1_B12") (pinfunction "GND_A1_B12") (pintype "power_in"))
      (node (ref "J4") (pin "SH1") (pinfunction "SHIELD_SH1") (pintype "passive"))
      (node (ref "J4") (pin "SH2") (pinfunction "SHIELD_SH2") (pintype "passive"))
      (node (ref "J4") (pin "SH3") (pinfunction "SHIELD_SH3") (pintype "passive"))
      (node (ref "J4") (pin "SH4") (pinfunction "SHIELD_SH4") (pintype "passive"))
      (node (ref "R1_USB") (pin "1") (pinfunction "1_1") (pintype "bidirectional"))
      (node (ref "R2_EP_DR") (pin "1") (pinfunction "1_1") (pintype "bidirectional"))
      (node (ref "R2_USB") (pin "2") (pinfunction "2_2") (pintype "bidirectional"))
      (node (ref "R3") (pin "1") (pinfunction "1_1") (pintype "bidirectional"))
      (node (ref "R9") (pin "1") (pinfunction "1_1") (pintype "bidirectional"))
      (node (ref "R_TYPE_SEL") (pin "1") (pinfunction "1_1") (pintype "bidirectional"))
      (node (ref "SJ1") (pin "1") (pinfunction "1_1") (pintype "passive"))
      (node (ref "SW_DN") (pin "1") (pinfunction "1_1") (pintype "passive"))
      (node (ref "SW_ENT") (pin "1") (pinfunction "1_1") (pintype "passive"))
      (node (ref "SW_UP") (pin "1") (pinfunction "1_1") (pintype "passive"))
      (node (ref "TP_BAT_GND") (pin "TP") (pinfunction "TP_TP") (pintype "input"))
      (node (ref "TP_GND") (pin "TP") (pinfunction "TP_TP") (pintype "input"))
      (node (ref "U1") (pin "P$74") (pinfunction "VSS_PAD_P$74") (pintype "bidirectional"))
      (node (ref "U1") (pin "P$75") (pinfunction "VSS_PAD_P$75") (pintype "bidirectional"))
      (node (ref "U1") (pin "P$76") (pinfunction "VSS_PAD_P$76") (pintype "bidirectional"))
      (node (ref "U1") (pin "P$77") (pinfunction "VSS_PAD_P$77") (pintype "bidirectional"))
      (node (ref "U1") (pin "P$78") (pinfunction "VSS_PAD_P$78") (pintype "bidirectional"))
      (node (ref "U1") (pin "P$79") (pinfunction "VSS_PAD_P$79") (pintype "bidirectional"))
      (node (ref "U1") (pin "P$80") (pinfunction "VSS_PAD_P$80") (pintype "bidirectional"))
      (node (ref "U1") (pin "P$81") (pinfunction "VSS_PAD_P$81") (pintype "bidirectional"))
      (node (ref "U1") (pin "P$82") (pinfunction "VSS_PAD_P$82") (pintype "bidirectional"))
      (node (ref "U1") (pin "P$83") (pinfunction "VSS_PAD_P$83") (pintype "bidirectional"))
      (node (ref "U1") (pin "P$84") (pinfunction "VSS_PAD_P$84") (pintype "bidirectional"))
      (node (ref "U1") (pin "P$85") (pinfunction "VSS_PAD_P$85") (pintype "bidirectional"))
      (node (ref "U1") (pin "P$86") (pinfunction "VSS_PAD_P$86") (pintype "bidirectional"))
      (node (ref "U1") (pin "P$87") (pinfunction "VSS_PAD_P$87") (pintype "bidirectional"))
      (node (ref "U1") (pin "P$88") (pinfunction "VSS_PAD_P$88") (pintype "bidirectional"))
      (node (ref "U1") (pin "P$89") (pinfunction "VSS_PAD_P$89") (pintype "bidirectional"))
      (node (ref "U1") (pin "P$90") (pinfunction "VSS_PAD_P$90") (pintype "bidirectional"))
      (node (ref "U1") (pin "P$B7") (pinfunction "VSS_P$B7") (pintype "power_in"))
      (node (ref "U1") (pin "P$F23") (pinfunction "VSS_PA_P$F23") (pintype "bidirectional"))
      (node (ref "U3") (pin "1") (pinfunction "CTG_1") (pintype "power_in"))
      (node (ref "U3") (pin "4") (pinfunction "GND_4") (pintype "power_in"))
      (node (ref "U3") (pin "6") (pinfunction "QSTRT_6") (pintype "input"))
      (node (ref "U3") (pin "9") (pinfunction "EP_9") (pintype "power_in"))
      (node (ref "X1") (pin "2") (pinfunction "2_2") (pintype "passive"))
      (node (ref "X1") (pin "4") (pinfunction "4_4") (pintype "passive"))
    )
    (net (code "25") (name "HAPTIC_EN{slash}1.4C") (class "Default")
      (node (ref "IC2") (pin "A1") (pinfunction "EN_A1") (pintype "bidirectional"))
    )
    (net (code "26") (name "HAPTIC_EN{slash}2.6A") (class "Default")
      (node (ref "U1") (pin "P$U1") (pinfunction "P0.12_P$U1") (pintype "bidirectional"))
    )
    (net (code "27") (name "IMU_INT1") (class "Default")
      (node (ref "IC3") (pin "5") (pinfunction "INT1_5") (pintype "bidirectional"))
      (node (ref "U1") (pin "P$N1") (pinfunction "P0.08_P$N1") (pintype "bidirectional"))
    )
    (net (code "28") (name "IMU_INT2") (class "Default")
      (node (ref "IC3") (pin "6") (pinfunction "INT2_6") (pintype "bidirectional"))
      (node (ref "U1") (pin "P$P2") (pinfunction "P1.08_P$P2") (pintype "bidirectional"))
    )
    (net (code "29") (name "LX1") (class "Default")
      (node (ref "IC9") (pin "B2") (pinfunction "SW1_1_B2") (pintype "bidirectional"))
      (node (ref "IC9") (pin "B3") (pinfunction "SW1_2_B3") (pintype "bidirectional"))
      (node (ref "L7") (pin "1") (pinfunction "1_1") (pintype "bidirectional"))
    )
    (net (code "30") (name "LX2") (class "Default")
      (node (ref "IC9") (pin "D2") (pinfunction "SW2_1_D2") (pintype "bidirectional"))
      (node (ref "IC9") (pin "D3") (pinfunction "SW2_2_D3") (pintype "bidirectional"))
      (node (ref "L7") (pin "2") (pinfunction "2_2") (pintype "bidirectional"))
    )
    (net (code "31") (name "MOSI{slash}1.5B") (class "Default")
      (node (ref "J1") (pin "14") (pinfunction "14_14") (pintype "bidirectional"))
    )
    (net (code "32") (name "MOS{slash}2.2D") (class "Default")
      (node (ref "U1") (pin "P$B13") (pinfunction "P0.03/AIN1_P$B13") (pintype "bidirectional"))
    )
    (net (code "33") (name "N$6") (class "Default")
      (node (ref "C25") (pin "1") (pinfunction "1_1") (pintype "passive"))
      (node (ref "C33") (pin "1") (pinfunction "1_1") (pintype "passive"))
      (node (ref "IC9") (pin "E2") (pinfunction "VOUT_1_E2") (pintype "bidirectional"))
      (node (ref "IC9") (pin "E3") (pinfunction "VOUT_2_E3") (pintype "bidirectional"))
    )
    (net (code "34") (name "Net-(ANT1-FEED)") (class "Default")
      (node (ref "ANT1") (pin "1") (pinfunction "FEED_1") (pintype "input"))
      (node (ref "C22") (pin "1") (pinfunction "1_1") (pintype "passive"))
      (node (ref "C4") (pin "1") (pinfunction "1_1") (pintype "passive"))
      (node (ref "L1") (pin "2") (pinfunction "2_2") (pintype "passive"))
    )
    (net (code "35") (name "Net-(D2-K)") (class "Default")
      (node (ref "C2-EP-DR") (pin "1") (pinfunction "1_1") (pintype "passive"))
      (node (ref "D2") (pin "1") (pinfunction "K_1") (pintype "bidirectional"))
      (node (ref "D4") (pin "2") (pinfunction "A_2") (pintype "bidirectional"))
    )
    (net (code "36") (name "Net-(D5-A)") (class "Default")
      (node (ref "C2-EP-DR") (pin "2") (pinfunction "2_2") (pintype "passive"))
      (node (ref "D5") (pin "2") (pinfunction "A_2") (pintype "bidirectional"))
      (node (ref "L5") (pin "2") (pinfunction "2_2") (pintype "passive"))
      (node (ref "Q3") (pin "3") (pinfunction "D_3") (pintype "bidirectional"))
    )
    (net (code "37") (name "Net-(EPD_C1-Pad2)") (class "Default")
      (node (ref "EPD_C1") (pin "2") (pinfunction "2_2") (pintype "passive"))
      (node (ref "J1") (pin "5") (pinfunction "5_5") (pintype "bidirectional"))
    )
    (net (code "38") (name "Net-(EPD_C2-Pad2)") (class "Default")
      (node (ref "EPD_C2") (pin "2") (pinfunction "2_2") (pintype "passive"))
      (node (ref "J1") (pin "4") (pinfunction "4_4") (pintype "bidirectional"))
    )
    (net (code "39") (name "Net-(EPD_C6-Pad2)") (class "Default")
      (node (ref "EPD_C6") (pin "2") (pinfunction "2_2") (pintype "passive"))
      (node (ref "J1") (pin "18") (pinfunction "18_18") (pintype "bidirectional"))
    )
    (net (code "40") (name "Net-(EPD_C7-Pad2)") (class "Default")
      (node (ref "EPD_C7") (pin "2") (pinfunction "2_2") (pintype "passive"))
      (node (ref "J1") (pin "19") (pinfunction "19_19") (pintype "bidirectional"))
    )
    (net (code "41") (name "Net-(EPD_C8-Pad2)") (class "Default")
      (node (ref "EPD_C8") (pin "2") (pinfunction "2_2") (pintype "passive"))
      (node (ref "J1") (pin "20") (pinfunction "20_20") (pintype "bidirectional"))
    )
    (net (code "42") (name "Net-(EPD_C10-Pad2)") (class "Default")
      (node (ref "EPD_C10") (pin "2") (pinfunction "2_2") (pintype "passive"))
      (node (ref "J1") (pin "22") (pinfunction "22_22") (pintype "bidirectional"))
    )
    (net (code "43") (name "Net-(EPD_C12-Pad2)") (class "Default")
      (node (ref "EPD_C12") (pin "2") (pinfunction "2_2") (pintype "passive"))
      (node (ref "J1") (pin "24") (pinfunction "24_24") (pintype "bidirectional"))
    )
    (net (code "44") (name "Net-(IC1-TS{slash}MR)") (class "Default")
      (node (ref "IC1") (pin "D1") (pinfunction "TS/MR_D1") (pintype "bidirectional"))
      (node (ref "R9") (pin "2") (pinfunction "2_2") (pintype "bidirectional"))
    )
    (net (code "45") (name "Net-(IC2-REG)") (class "Default")
      (node (ref "C32") (pin "2") (pinfunction "2_2") (pintype "passive"))
      (node (ref "IC2") (pin "A2") (pinfunction "REG_A2") (pintype "bidirectional"))
    )
    (net (code "46") (name "Net-(IC3-SDO)") (class "Default")
      (node (ref "IC3") (pin "1") (pinfunction "SDO_1") (pintype "bidirectional"))
      (node (ref "R3") (pin "2") (pinfunction "2_2") (pintype "bidirectional"))
    )
    (net (code "47") (name "Net-(IC9-SCL)") (class "Default")
      (node (ref "IC9") (pin "D1") (pinfunction "SCL_D1") (pintype "bidirectional"))
      (node (ref "R4") (pin "2") (pinfunction "2_2") (pintype "bidirectional"))
    )
    (net (code "48") (name "Net-(IC9-SDA)") (class "Default")
      (node (ref "IC9") (pin "E1") (pinfunction "SDA_E1") (pintype "bidirectional"))
      (node (ref "R2") (pin "2") (pinfunction "2_2") (pintype "bidirectional"))
    )
    (net (code "49") (name "Net-(J4-CC1)") (class "Default")
      (node (ref "J4") (pin "A5") (pinfunction "CC1_A5") (pintype "bidirectional"))
      (node (ref "R1_USB") (pin "2") (pinfunction "2_2") (pintype "bidirectional"))
    )
    (net (code "50") (name "Net-(J4-CC2)") (class "Default")
      (node (ref "J4") (pin "B5") (pinfunction "CC2_B5") (pintype "bidirectional"))
      (node (ref "R2_USB") (pin "1") (pinfunction "1_1") (pintype "bidirectional"))
    )
    (net (code "51") (name "Net-(L2-Pad2)") (class "Default")
      (node (ref "L2") (pin "2") (pinfunction "2_2") (pintype "passive"))
      (node (ref "L3") (pin "1") (pinfunction "1_1") (pintype "passive"))
    )
    (net (code "52") (name "Net-(R1_EP_DR-Pad1)") (class "Default")
      (node (ref "R1_EP_DR") (pin "1") (pinfunction "1_1") (pintype "bidirectional"))
      (node (ref "R_TYPE_SEL") (pin "2") (pinfunction "2_2") (pintype "bidirectional"))
      (node (ref "SJ1") (pin "2") (pinfunction "2_2") (pintype "passive"))
    )
    (net (code "53") (name "Net-(U1-ANT)") (class "Default")
      (node (ref "C3") (pin "1") (pinfunction "1_1") (pintype "passive"))
      (node (ref "L1") (pin "1") (pinfunction "1_1") (pintype "passive"))
      (node (ref "U1") (pin "P$H23") (pinfunction "ANT_P$H23") (pintype "bidirectional"))
    )
    (net (code "54") (name "Net-(U1-DCC)") (class "Default")
      (node (ref "L2") (pin "1") (pinfunction "1_1") (pintype "passive"))
      (node (ref "U1") (pin "P$B3") (pinfunction "DCC_P$B3") (pintype "output"))
    )
    (net (code "55") (name "Net-(U1-DEC2)") (class "Default")
      (node (ref "C13") (pin "1") (pinfunction "1_1") (pintype "passive"))
      (node (ref "U1") (pin "P$A18") (pinfunction "DEC2_P$A18") (pintype "bidirectional"))
    )
    (net (code "56") (name "Net-(U1-DEC3V3)") (class "Default")
      (node (ref "C20") (pin "1") (pinfunction "1_1") (pintype "passive"))
      (node (ref "U1") (pin "P$AC5") (pinfunction "DEC3V3_P$AC5") (pintype "bidirectional"))
    )
    (net (code "57") (name "Net-(U1-DEC5)") (class "Default")
      (node (ref "C9") (pin "1") (pinfunction "1_1") (pintype "passive"))
      (node (ref "U1") (pin "P$N24") (pinfunction "DEC5_P$N24") (pintype "bidirectional"))
    )
    (net (code "58") (name "Net-(U1-XC1)") (class "Default")
      (node (ref "C1") (pin "1") (pinfunction "1_1") (pintype "passive"))
      (node (ref "U1") (pin "P$B24") (pinfunction "XC1_P$B24") (pintype "input"))
      (node (ref "X1") (pin "1") (pinfunction "1_1") (pintype "passive"))
    )
    (net (code "59") (name "Net-(U1-XC2)") (class "Default")
      (node (ref "C2") (pin "1") (pinfunction "1_1") (pintype "passive"))
      (node (ref "U1") (pin "P$A23") (pinfunction "XC2_P$A23") (pintype "output"))
      (node (ref "X1") (pin "3") (pinfunction "3_3") (pintype "passive"))
    )
    (net (code "60") (name "OUT+") (class "Default")
      (node (ref "IC2") (pin "A3") (pinfunction "OUT+_A3") (pintype "bidirectional"))
      (node (ref "TP_OP") (pin "TP") (pinfunction "TP_TP") (pintype "input"))
    )
    (net (code "61") (name "OUT-") (class "Default")
      (node (ref "IC2") (pin "C3") (pinfunction "OUT-_C3") (pintype "bidirectional"))
      (node (ref "TP_ON") (pin "TP") (pinfunction "TP_TP") (pintype "input"))
    )
    (net (code "62") (name "P0.00{slash}XL1") (class "Default")
      (node (ref "C17") (pin "2") (pinfunction "2_2") (pintype "passive"))
      (node (ref "U1") (pin "P$D2") (pinfunction "P0.00/XL1_P$D2") (pintype "bidirectional"))
      (node (ref "X2") (pin "1") (pinfunction "1_1") (pintype "passive"))
    )
    (net (code "63") (name "P0.01{slash}XL2") (class "Default")
      (node (ref "C18") (pin "2") (pinfunction "2_2") (pintype "passive"))
      (node (ref "U1") (pin "P$F2") (pinfunction "P0.01/XL2_P$F2") (pintype "bidirectional"))
      (node (ref "X2") (pin "2") (pinfunction "2_2") (pintype "passive"))
    )
    (net (code "64") (name "P0.04") (class "Default")
      (node (ref "U1") (pin "P$J1") (pinfunction "P0.04/AIN2_P$J1") (pintype "bidirectional"))
    )
    (net (code "65") (name "P0.09") (class "Default")
      (node (ref "U1") (pin "P$L24") (pinfunction "P0.09/NFC1_P$L24") (pintype "bidirectional"))
    )
    (net (code "66") (name "P0.13{slash}1.5D") (class "Default")
      (node (ref "C30") (pin "2") (pinfunction "2_2") (pintype "passive"))
      (node (ref "R5") (pin "1") (pinfunction "1_1") (pintype "bidirectional"))
      (node (ref "SW_UP") (pin "2") (pinfunction "2_2") (pintype "passive"))
    )
    (net (code "67") (name "P0.13{slash}2.6C") (class "Default")
      (node (ref "U1") (pin "P$AD8") (pinfunction "P0.13_P$AD8") (pintype "bidirectional"))
    )
    (net (code "68") (name "P0.14{slash}1.5D") (class "Default")
      (node (ref "C31") (pin "2") (pinfunction "2_2") (pintype "passive"))
      (node (ref "R8") (pin "1") (pinfunction "1_1") (pintype "bidirectional"))
      (node (ref "SW_ENT") (pin "2") (pinfunction "2_2") (pintype "passive"))
    )
    (net (code "69") (name "P0.14{slash}2.7C") (class "Default")
      (node (ref "U1") (pin "P$AC9") (pinfunction "P0.14_P$AC9") (pintype "bidirectional"))
    )
    (net (code "70") (name "P0.19") (class "Default")
      (node (ref "U1") (pin "P$AC15") (pinfunction "P0.19_P$AC15") (pintype "bidirectional"))
    )
    (net (code "71") (name "P0.20") (class "Default")
      (node (ref "U1") (pin "P$AD16") (pinfunction "P0.20_P$AD16") (pintype "bidirectional"))
    )
    (net (code "72") (name "P0.21") (class "Default")
      (node (ref "U1") (pin "P$AC17") (pinfunction "P0.21_P$AC17") (pintype "bidirectional"))
    )
    (net (code "73") (name "P0.22") (class "Default")
      (node (ref "U1") (pin "P$AD18") (pinfunction "P0.22_P$AD18") (pintype "bidirectional"))
    )
    (net (code "74") (name "P0.23") (class "Default")
      (node (ref "U1") (pin "P$AC19") (pinfunction "P0.23_P$AC19") (pintype "bidirectional"))
    )
    (net (code "75") (name "P0.24") (class "Default")
      (node (ref "U1") (pin "P$AD20") (pinfunction "P0.24_P$AD20") (pintype "bidirectional"))
    )
    (net (code "76") (name "P0.25") (class "Default")
      (node (ref "U1") (pin "P$AC21") (pinfunction "P0.25_P$AC21") (pintype "bidirectional"))
    )
    (net (code "77") (name "P0.26") (class "Default")
      (node (ref "U1") (pin "P$G1") (pinfunction "P0.26_P$G1") (pintype "bidirectional"))
    )
    (net (code "78") (name "P0.27") (class "Default")
      (node (ref "U1") (pin "P$H2") (pinfunction "P0.27_P$H2") (pintype "bidirectional"))
    )
    (net (code "79") (name "P0.28") (class "Default")
      (node (ref "U1") (pin "P$B11") (pinfunction "P0.28/AIN4_P$B11") (pintype "bidirectional"))
    )
    (net (code "80") (name "P0.29") (class "Default")
      (node (ref "U1") (pin "P$A10") (pinfunction "P0.29/AIN5_P$A10") (pintype "bidirectional"))
    )
    (net (code "81") (name "P0.30") (class "Default")
      (node (ref "U1") (pin "P$B9") (pinfunction "P0.30/AIN6_P$B9") (pintype "bidirectional"))
    )
    (net (code "82") (name "P0.31") (class "Default")
      (node (ref "U1") (pin "P$A8") (pinfunction "P0.31/AIN7_P$A8") (pintype "bidirectional"))
    )
    (net (code "83") (name "P1.01{slash}1.6C") (class "Default")
      (node (ref "DMG2305UX-7") (pin "1") (pinfunction "G_1") (pintype "bidirectional"))
      (node (ref "R_PWR_EPD") (pin "1") (pinfunction "1_1") (pintype "bidirectional"))
    )
    (net (code "84") (name "P1.01{slash}2.4B") (class "Default")
      (node (ref "U1") (pin "P$Y23") (pinfunction "P1.01_P$Y23") (pintype "bidirectional"))
    )
    (net (code "85") (name "P1.02{slash}1.6C") (class "Default")
      (node (ref "C29") (pin "2") (pinfunction "2_2") (pintype "passive"))
      (node (ref "R7") (pin "1") (pinfunction "1_1") (pintype "bidirectional"))
      (node (ref "SW_DN") (pin "2") (pinfunction "2_2") (pintype "passive"))
    )
    (net (code "86") (name "P1.02{slash}2.8C") (class "Default")
      (node (ref "U1") (pin "P$W24") (pinfunction "P1.02_P$W24") (pintype "bidirectional"))
    )
    (net (code "87") (name "P1.03") (class "Default")
      (node (ref "U1") (pin "P$V23") (pinfunction "P1.03_P$V23") (pintype "bidirectional"))
    )
    (net (code "88") (name "P1.04") (class "Default")
      (node (ref "U1") (pin "P$U24") (pinfunction "P1.04_P$U24") (pintype "bidirectional"))
    )
    (net (code "89") (name "P1.05") (class "Default")
      (node (ref "U1") (pin "P$T23") (pinfunction "P1.05_P$T23") (pintype "bidirectional"))
    )
    (net (code "90") (name "P1.06") (class "Default")
      (node (ref "U1") (pin "P$R24") (pinfunction "P1.06_P$R24") (pintype "bidirectional"))
    )
    (net (code "91") (name "P1.07") (class "Default")
      (node (ref "U1") (pin "P$P23") (pinfunction "P1.07_P$P23") (pintype "bidirectional"))
    )
    (net (code "92") (name "P1.09") (class "Default")
      (node (ref "U1") (pin "P$R1") (pinfunction "P1.09_P$R1") (pintype "bidirectional"))
    )
    (net (code "93") (name "P1.10") (class "Default")
      (node (ref "U1") (pin "P$A20") (pinfunction "P1.10_P$A20") (pintype "bidirectional"))
    )
    (net (code "94") (name "P1.11") (class "Default")
      (node (ref "U1") (pin "P$B19") (pinfunction "P1.11_P$B19") (pintype "bidirectional"))
    )
    (net (code "95") (name "P1.12") (class "Default")
      (node (ref "U1") (pin "P$B17") (pinfunction "P1.12_P$B17") (pintype "bidirectional"))
    )
    (net (code "96") (name "P1.13") (class "Default")
      (node (ref "U1") (pin "P$A16") (pinfunction "P1.13_P$A16") (pintype "bidirectional"))
    )
    (net (code "97") (name "P1.14") (class "Default")
      (node (ref "U1") (pin "P$B15") (pinfunction "P1.14_P$B15") (pintype "bidirectional"))
    )
    (net (code "98") (name "P1.15") (class "Default")
      (node (ref "U1") (pin "P$A14") (pinfunction "P1.15_P$A14") (pintype "bidirectional"))
    )
    (net (code "99") (name "PMIC_INT") (class "Default")
      (node (ref "IC1") (pin "A1") (pinfunction "~{INT}_A1") (pintype "bidirectional"))
      (node (ref "U1") (pin "P$T2") (pinfunction "P0.11_P$T2") (pintype "bidirectional"))
    )
    (net (code "100") (name "PREVGH") (class "Default")
      (node (ref "D5") (pin "1") (pinfunction "K_1") (pintype "bidirectional"))
      (node (ref "EPD_C9") (pin "2") (pinfunction "2_2") (pintype "passive"))
      (node (ref "J1") (pin "21") (pinfunction "21_21") (pintype "bidirectional"))
    )
    (net (code "101") (name "PREVGL") (class "Default")
      (node (ref "D2") (pin "2") (pinfunction "A_2") (pintype "bidirectional"))
      (node (ref "EPD_C11") (pin "2") (pinfunction "2_2") (pintype "passive"))
      (node (ref "J1") (pin "23") (pinfunction "23_23") (pintype "bidirectional"))
    )
    (net (code "102") (name "RESE") (class "Default")
      (node (ref "J1") (pin "3") (pinfunction "3_3") (pintype "bidirectional"))
      (node (ref "Q3") (pin "2") (pinfunction "S_2") (pintype "bidirectional"))
      (node (ref "R1_EP_DR") (pin "2") (pinfunction "2_2") (pintype "bidirectional"))
    )
    (net (code "103") (name "RESET") (class "Default")
      (node (ref "J2") (pin "6") (pinfunction "6_6") (pintype "bidirectional"))
      (node (ref "TP_RESET") (pin "TP") (pinfunction "TP_TP") (pintype "input"))
      (node (ref "U1") (pin "P$AC13") (pinfunction "P0.18/RESET_P$AC13") (pintype "bidirectional"))
    )
    (net (code "104") (name "SCK{slash}1.5B") (class "Default")
      (node (ref "J1") (pin "13") (pinfunction "13_13") (pintype "bidirectional"))
    )
    (net (code "105") (name "SCK{slash}2.2D") (class "Default")
      (node (ref "U1") (pin "P$A12") (pinfunction "P0.02/AIN0_P$A12") (pintype "bidirectional"))
    )
    (net (code "106") (name "SCL{slash}1.4C") (class "Default")
      (node (ref "IC2") (pin "C1") (pinfunction "SCL_C1") (pintype "bidirectional"))
      (node (ref "U3") (pin "7") (pinfunction "SCL_7") (pintype "input"))
    )
    (net (code "107") (name "SCL{slash}2.4C") (class "Default")
      (node (ref "IC1") (pin "B1") (pinfunction "SCL_B1") (pintype "bidirectional"))
      (node (ref "IC3") (pin "12") (pinfunction "SCX_12") (pintype "bidirectional"))
      (node (ref "R17") (pin "2") (pinfunction "2_2") (pintype "bidirectional"))
      (node (ref "R4") (pin "1") (pinfunction "1_1") (pintype "bidirectional"))
      (node (ref "TP1") (pin "TP") (pinfunction "TP_TP") (pintype "input"))
      (node (ref "U1") (pin "P$M2") (pinfunction "P0.07_P$M2") (pintype "bidirectional"))
    )
    (net (code "108") (name "SDA{slash}1.4C") (class "Default")
      (node (ref "IC2") (pin "B2") (pinfunction "SDA_B2") (pintype "bidirectional"))
      (node (ref "U3") (pin "8") (pinfunction "SDA_8") (pintype "bidirectional"))
    )
    (net (code "109") (name "SDA{slash}2.4C") (class "Default")
      (node (ref "IC1") (pin "C1") (pinfunction "SDA_C1") (pintype "bidirectional"))
      (node (ref "IC3") (pin "2") (pinfunction "SDX_2") (pintype "bidirectional"))
      (node (ref "R18") (pin "2") (pinfunction "2_2") (pintype "bidirectional"))
      (node (ref "R2") (pin "1") (pinfunction "1_1") (pintype "bidirectional"))
      (node (ref "TP2") (pin "TP") (pinfunction "TP_TP") (pintype "input"))
      (node (ref "U1") (pin "P$L1") (pinfunction "P0.06_P$L1") (pintype "bidirectional"))
    )
    (net (code "110") (name "SWDCLK") (class "Default")
      (node (ref "J2") (pin "4") (pinfunction "4_4") (pintype "bidirectional"))
      (node (ref "TP_SWDCLK") (pin "TP") (pinfunction "TP_TP") (pintype "input"))
      (node (ref "U1") (pin "P$AA24") (pinfunction "SWDCLK_P$AA24") (pintype "input"))
    )
    (net (code "111") (name "SWDIO") (class "Default")
      (node (ref "J2") (pin "2") (pinfunction "2_2") (pintype "bidirectional"))
      (node (ref "TP_SWDIO") (pin "TP") (pinfunction "TP_TP") (pintype "input"))
      (node (ref "U1") (pin "P$AC24") (pinfunction "SWDIO_P$AC24") (pintype "bidirectional"))
    )
    (net (code "112") (name "SWO") (class "Default")
      (node (ref "TP_SWO") (pin "TP") (pinfunction "TP_TP") (pintype "input"))
      (node (ref "U1") (pin "P$AD22") (pinfunction "P1.00_P$AD22") (pintype "bidirectional"))
    )
    (net (code "113") (name "VBAT{slash}1.2A") (class "Default")
      (node (ref "C27") (pin "2") (pinfunction "2_2") (pintype "passive"))
      (node (ref "TP_VBAT") (pin "TP") (pinfunction "TP_TP") (pintype "input"))
      (node (ref "U3") (pin "2") (pinfunction "CELL_2") (pintype "power_in"))
      (node (ref "U3") (pin "3") (pinfunction "VDD_3") (pintype "power_in"))
    )
    (net (code "114") (name "VBAT{slash}2.5C") (class "Default")
      (node (ref "C37") (pin "1") (pinfunction "1_1") (pintype "passive"))
      (node (ref "IC1") (pin "C2") (pinfunction "BAT_C2") (pintype "bidirectional"))
    )
    (net (code "115") (name "VBUS{slash}1.5D") (class "Default")
      (node (ref "C42") (pin "1") (pinfunction "1_1") (pintype "passive"))
      (node (ref "C43") (pin "1") (pinfunction "1_1") (pintype "passive"))
      (node (ref "D3") (pin "5") (pinfunction "VBUS_5") (pintype "bidirectional"))
      (node (ref "J4") (pin "A4_B9") (pinfunction "VBUS_A4_B9") (pintype "power_in"))
      (node (ref "J4") (pin "A9_B4") (pinfunction "VBUS_A9_B4") (pintype "power_in"))
    )
    (net (code "116") (name "VBUS{slash}2.6D") (class "Default")
      (node (ref "C21") (pin "1") (pinfunction "1_1") (pintype "passive"))
      (node (ref "C38") (pin "1") (pinfunction "1_1") (pintype "passive"))
      (node (ref "IC1") (pin "A2") (pinfunction "IN_A2") (pintype "bidirectional"))
      (node (ref "U1") (pin "P$AD2") (pinfunction "VBUS_P$AD2") (pintype "power_in"))
    )
    (net (code "117") (name "VREG") (class "Default")
      (node (ref "C23") (pin "2") (pinfunction "2_2") (pintype "passive"))
      (node (ref "C24") (pin "2") (pinfunction "2_2") (pintype "passive"))
      (node (ref "C39") (pin "1") (pinfunction "1_1") (pintype "passive"))
      (node (ref "IC1") (pin "B2") (pinfunction "SYS_B2") (pintype "bidirectional"))
      (node (ref "IC9") (pin "A1") (pinfunction "EN_A1") (pintype "bidirectional"))
      (node (ref "IC9") (pin "A2") (pinfunction "VIN_1_A2") (pintype "bidirectional"))
      (node (ref "IC9") (pin "A3") (pinfunction "VIN_2_A3") (pintype "bidirectional"))
      (node (ref "TP_VREG") (pin "TP") (pinfunction "TP_TP") (pintype "input"))
    )
    (net (code "118") (name "unconnected-(ANT1-NC-Pad2)") (class "Default")
      (node (ref "ANT1") (pin "2") (pinfunction "NC_2") (pintype "no_connect"))
    )
    (net (code "119") (name "unconnected-(IC3-ASCL-Pad11)") (class "Default")
      (node (ref "IC3") (pin "11") (pinfunction "ASCL_11") (pintype "bidirectional"))
    )
    (net (code "120") (name "unconnected-(IC3-ASDA-Pad4)") (class "Default")
      (node (ref "IC3") (pin "4") (pinfunction "ASDA_4") (pintype "bidirectional"))
    )
    (net (code "121") (name "unconnected-(J1-Pad1)") (class "Default")
      (node (ref "J1") (pin "1") (pinfunction "1_1") (pintype "bidirectional"))
    )
    (net (code "122") (name "unconnected-(J1-Pad6)") (class "Default")
      (node (ref "J1") (pin "6") (pinfunction "6_6") (pintype "bidirectional"))
    )
    (net (code "123") (name "unconnected-(J1-Pad7)") (class "Default")
      (node (ref "J1") (pin "7") (pinfunction "7_7") (pintype "bidirectional"))
    )
    (net (code "124") (name "unconnected-(J4-SBU1-PadA8)") (class "Default")
      (node (ref "J4") (pin "A8") (pinfunction "SBU1_A8") (pintype "bidirectional"))
    )
    (net (code "125") (name "unconnected-(J4-SBU2-PadB8)") (class "Default")
      (node (ref "J4") (pin "B8") (pinfunction "SBU2_B8") (pintype "bidirectional"))
    )
    (net (code "126") (name "unconnected-(U1-DCCH-PadP$AB2)") (class "Default")
      (node (ref "U1") (pin "P$AB2") (pinfunction "DCCH_P$AB2") (pintype "bidirectional"))
    )
  )
)
